# Side_1.net
KiCad netlist of a schematic drawn in EAGLE
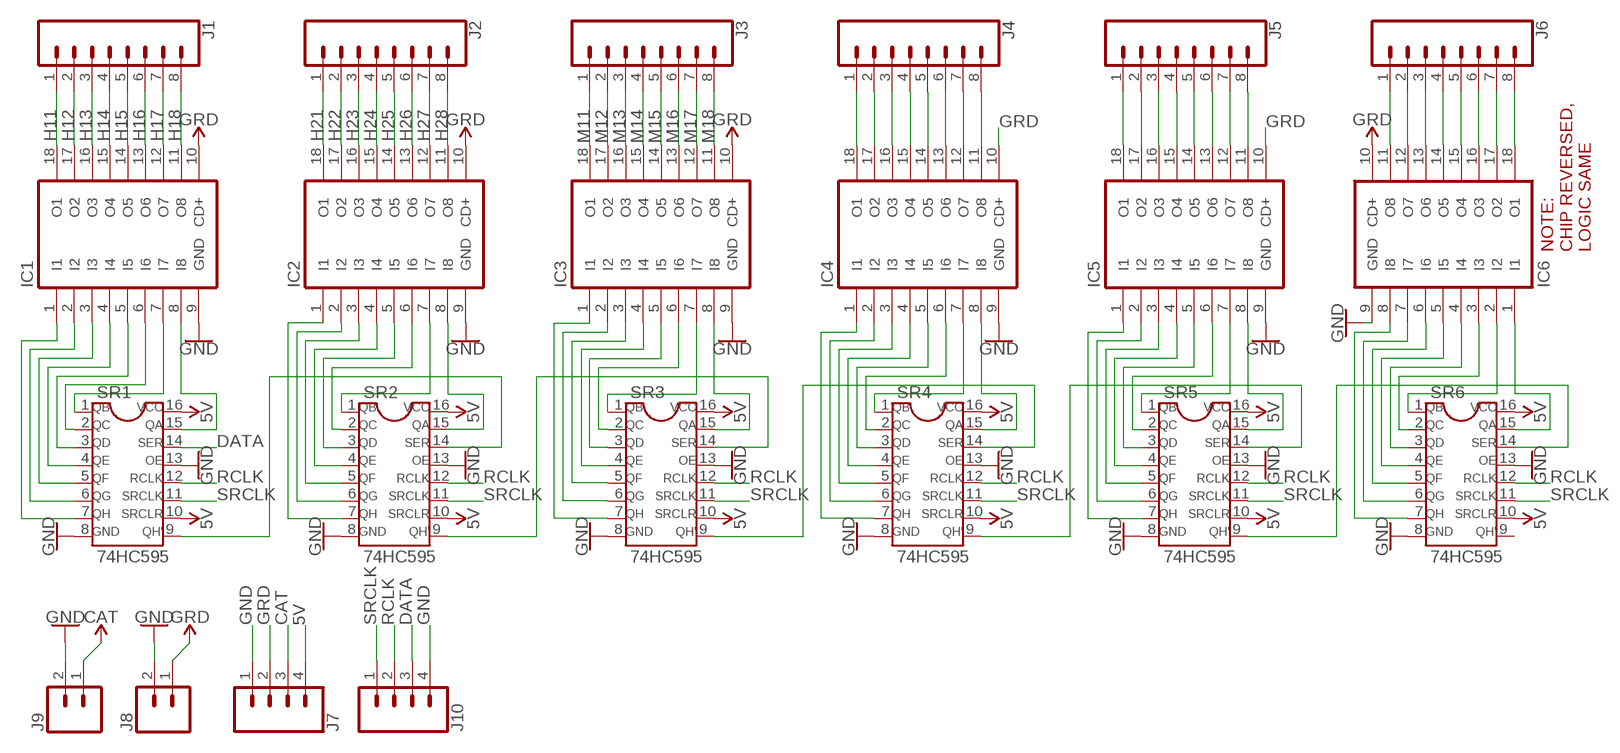
[diagram p0: schematic, sheet 1]

(export (version "E")
  (design (tool "Eeschema 10.0.6"))
  (components
    (comp (ref "IC1")
      (value "ULN2802A")
      (footprint "eagle-import:DIL18")
      (libsource (lib "eagle-import") (part "ULN2802A"))
    )
    (comp (ref "IC2")
      (value "ULN2802A")
      (footprint "eagle-import:DIL18")
      (libsource (lib "eagle-import") (part "ULN2802A"))
    )
    (comp (ref "IC3")
      (value "ULN2802A")
      (footprint "eagle-import:DIL18")
      (libsource (lib "eagle-import") (part "ULN2802A"))
    )
    (comp (ref "IC4")
      (value "ULN2802A")
      (footprint "eagle-import:DIL18")
      (libsource (lib "eagle-import") (part "ULN2802A"))
    )
    (comp (ref "IC5")
      (value "ULN2802A")
      (footprint "eagle-import:DIL18")
      (libsource (lib "eagle-import") (part "ULN2802A"))
    )
    (comp (ref "IC6")
      (value "ULN2802A")
      (footprint "eagle-import:DIL18")
      (libsource (lib "eagle-import") (part "ULN2802A"))
    )
    (comp (ref "J1")
      (value "CONN_08\"")
      (footprint "eagle-import:1X08")
      (libsource (lib "eagle-import") (part "CONN_08{dblquote}"))
    )
    (comp (ref "J2")
      (value "CONN_08\"")
      (footprint "eagle-import:1X08")
      (libsource (lib "eagle-import") (part "CONN_08{dblquote}"))
    )
    (comp (ref "J3")
      (value "CONN_08\"")
      (footprint "eagle-import:1X08")
      (libsource (lib "eagle-import") (part "CONN_08{dblquote}"))
    )
    (comp (ref "J4")
      (value "CONN_08\"")
      (footprint "eagle-import:1X08")
      (libsource (lib "eagle-import") (part "CONN_08{dblquote}"))
    )
    (comp (ref "J5")
      (value "CONN_08\"")
      (footprint "eagle-import:1X08")
      (libsource (lib "eagle-import") (part "CONN_08{dblquote}"))
    )
    (comp (ref "J6")
      (value "CONN_08\"")
      (footprint "eagle-import:1X08")
      (libsource (lib "eagle-import") (part "CONN_08{dblquote}"))
    )
    (comp (ref "J7")
      (value "CONN_04")
      (footprint "eagle-import:1X04")
      (libsource (lib "eagle-import") (part "CONN_04"))
    )
    (comp (ref "J8")
      (value "CONN_02")
      (footprint "eagle-import:1X02")
      (libsource (lib "eagle-import") (part "CONN_02"))
    )
    (comp (ref "J9")
      (value "CONN_02")
      (footprint "eagle-import:1X02")
      (libsource (lib "eagle-import") (part "CONN_02"))
    )
    (comp (ref "J10")
      (value "CONN_04")
      (footprint "eagle-import:1X04")
      (libsource (lib "eagle-import") (part "CONN_04"))
    )
    (comp (ref "SR1")
      (value "74HC595")
      (footprint "eagle-import:DIL16")
      (libsource (lib "eagle-import") (part "74HC595"))
    )
    (comp (ref "SR2")
      (value "74HC595")
      (footprint "eagle-import:DIL16")
      (libsource (lib "eagle-import") (part "74HC595"))
    )
    (comp (ref "SR3")
      (value "74HC595")
      (footprint "eagle-import:DIL16")
      (libsource (lib "eagle-import") (part "74HC595"))
    )
    (comp (ref "SR4")
      (value "74HC595")
      (footprint "eagle-import:DIL16")
      (libsource (lib "eagle-import") (part "74HC595"))
    )
    (comp (ref "SR5")
      (value "74HC595")
      (footprint "eagle-import:DIL16")
      (libsource (lib "eagle-import") (part "74HC595"))
    )
    (comp (ref "SR6")
      (value "74HC595")
      (footprint "eagle-import:DIL16")
      (libsource (lib "eagle-import") (part "74HC595"))
    )
  )
  (nets
    (net (code "1") (name "/DATA") (class "Default")
      (node (ref "J10") (pin "3") (pinfunction "3_3") (pintype "passive"))
      (node (ref "SR1") (pin "14") (pinfunction "SER_14") (pintype "passive"))
    )
    (net (code "2") (name "/H11") (class "Default")
      (node (ref "IC1") (pin "18") (pinfunction "O1_18") (pintype "open_collector"))
      (node (ref "J1") (pin "1") (pinfunction "1_1") (pintype "passive"))
    )
    (net (code "3") (name "/H12") (class "Default")
      (node (ref "IC1") (pin "17") (pinfunction "O2_17") (pintype "open_collector"))
      (node (ref "J1") (pin "2") (pinfunction "2_2") (pintype "passive"))
    )
    (net (code "4") (name "/H13") (class "Default")
      (node (ref "IC1") (pin "16") (pinfunction "O3_16") (pintype "open_collector"))
      (node (ref "J1") (pin "3") (pinfunction "3_3") (pintype "passive"))
    )
    (net (code "5") (name "/H14") (class "Default")
      (node (ref "IC1") (pin "15") (pinfunction "O4_15") (pintype "open_collector"))
      (node (ref "J1") (pin "4") (pinfunction "4_4") (pintype "passive"))
    )
    (net (code "6") (name "/H15") (class "Default")
      (node (ref "IC1") (pin "14") (pinfunction "O5_14") (pintype "open_collector"))
      (node (ref "J1") (pin "5") (pinfunction "5_5") (pintype "passive"))
    )
    (net (code "7") (name "/H16") (class "Default")
      (node (ref "IC1") (pin "13") (pinfunction "O6_13") (pintype "open_collector"))
      (node (ref "J1") (pin "6") (pinfunction "6_6") (pintype "passive"))
    )
    (net (code "8") (name "/H17") (class "Default")
      (node (ref "IC1") (pin "12") (pinfunction "O7_12") (pintype "open_collector"))
      (node (ref "J1") (pin "7") (pinfunction "7_7") (pintype "passive"))
    )
    (net (code "9") (name "/H18") (class "Default")
      (node (ref "IC1") (pin "11") (pinfunction "O8_11") (pintype "open_collector"))
      (node (ref "J1") (pin "8") (pinfunction "8_8") (pintype "passive"))
    )
    (net (code "10") (name "/H21") (class "Default")
      (node (ref "IC2") (pin "18") (pinfunction "O1_18") (pintype "open_collector"))
      (node (ref "J2") (pin "1") (pinfunction "1_1") (pintype "passive"))
    )
    (net (code "11") (name "/H22") (class "Default")
      (node (ref "IC2") (pin "17") (pinfunction "O2_17") (pintype "open_collector"))
      (node (ref "J2") (pin "2") (pinfunction "2_2") (pintype "passive"))
    )
    (net (code "12") (name "/H23") (class "Default")
      (node (ref "IC2") (pin "16") (pinfunction "O3_16") (pintype "open_collector"))
      (node (ref "J2") (pin "3") (pinfunction "3_3") (pintype "passive"))
    )
    (net (code "13") (name "/H24") (class "Default")
      (node (ref "IC2") (pin "15") (pinfunction "O4_15") (pintype "open_collector"))
      (node (ref "J2") (pin "4") (pinfunction "4_4") (pintype "passive"))
    )
    (net (code "14") (name "/H25") (class "Default")
      (node (ref "IC2") (pin "14") (pinfunction "O5_14") (pintype "open_collector"))
      (node (ref "J2") (pin "5") (pinfunction "5_5") (pintype "passive"))
    )
    (net (code "15") (name "/H26") (class "Default")
      (node (ref "IC2") (pin "13") (pinfunction "O6_13") (pintype "open_collector"))
      (node (ref "J2") (pin "6") (pinfunction "6_6") (pintype "passive"))
    )
    (net (code "16") (name "/H27") (class "Default")
      (node (ref "IC2") (pin "12") (pinfunction "O7_12") (pintype "open_collector"))
      (node (ref "J2") (pin "7") (pinfunction "7_7") (pintype "passive"))
    )
    (net (code "17") (name "/H28") (class "Default")
      (node (ref "IC2") (pin "11") (pinfunction "O8_11") (pintype "open_collector"))
      (node (ref "J2") (pin "8") (pinfunction "8_8") (pintype "passive"))
    )
    (net (code "18") (name "/M11") (class "Default")
      (node (ref "IC3") (pin "18") (pinfunction "O1_18") (pintype "open_collector"))
      (node (ref "J3") (pin "1") (pinfunction "1_1") (pintype "passive"))
    )
    (net (code "19") (name "/M12") (class "Default")
      (node (ref "IC3") (pin "17") (pinfunction "O2_17") (pintype "open_collector"))
      (node (ref "J3") (pin "2") (pinfunction "2_2") (pintype "passive"))
    )
    (net (code "20") (name "/M13") (class "Default")
      (node (ref "IC3") (pin "16") (pinfunction "O3_16") (pintype "open_collector"))
      (node (ref "J3") (pin "3") (pinfunction "3_3") (pintype "passive"))
    )
    (net (code "21") (name "/M14") (class "Default")
      (node (ref "IC3") (pin "15") (pinfunction "O4_15") (pintype "open_collector"))
      (node (ref "J3") (pin "4") (pinfunction "4_4") (pintype "passive"))
    )
    (net (code "22") (name "/M15") (class "Default")
      (node (ref "IC3") (pin "14") (pinfunction "O5_14") (pintype "open_collector"))
      (node (ref "J3") (pin "5") (pinfunction "5_5") (pintype "passive"))
    )
    (net (code "23") (name "/M16") (class "Default")
      (node (ref "IC3") (pin "13") (pinfunction "O6_13") (pintype "open_collector"))
      (node (ref "J3") (pin "6") (pinfunction "6_6") (pintype "passive"))
    )
    (net (code "24") (name "/M17") (class "Default")
      (node (ref "IC3") (pin "12") (pinfunction "O7_12") (pintype "open_collector"))
      (node (ref "J3") (pin "7") (pinfunction "7_7") (pintype "passive"))
    )
    (net (code "25") (name "/M18") (class "Default")
      (node (ref "IC3") (pin "11") (pinfunction "O8_11") (pintype "open_collector"))
      (node (ref "J3") (pin "8") (pinfunction "8_8") (pintype "passive"))
    )
    (net (code "26") (name "/RCLK") (class "Default")
      (node (ref "J10") (pin "2") (pinfunction "2_2") (pintype "passive"))
      (node (ref "SR1") (pin "12") (pinfunction "RCLK_12") (pintype "passive"))
      (node (ref "SR2") (pin "12") (pinfunction "RCLK_12") (pintype "passive"))
      (node (ref "SR3") (pin "12") (pinfunction "RCLK_12") (pintype "passive"))
      (node (ref "SR4") (pin "12") (pinfunction "RCLK_12") (pintype "passive"))
      (node (ref "SR5") (pin "12") (pinfunction "RCLK_12") (pintype "passive"))
      (node (ref "SR6") (pin "12") (pinfunction "RCLK_12") (pintype "passive"))
    )
    (net (code "27") (name "/SRCLK") (class "Default")
      (node (ref "J10") (pin "1") (pinfunction "1_1") (pintype "passive"))
      (node (ref "SR1") (pin "11") (pinfunction "SRCLK_11") (pintype "passive"))
      (node (ref "SR2") (pin "11") (pinfunction "SRCLK_11") (pintype "passive"))
      (node (ref "SR3") (pin "11") (pinfunction "SRCLK_11") (pintype "passive"))
      (node (ref "SR4") (pin "11") (pinfunction "SRCLK_11") (pintype "passive"))
      (node (ref "SR5") (pin "11") (pinfunction "SRCLK_11") (pintype "passive"))
      (node (ref "SR6") (pin "11") (pinfunction "SRCLK_11") (pintype "passive"))
    )
    (net (code "28") (name "5V") (class "Default")
      (node (ref "J7") (pin "4") (pinfunction "4_4") (pintype "passive"))
      (node (ref "SR1") (pin "10") (pinfunction "SRCLR_10") (pintype "passive"))
      (node (ref "SR1") (pin "16") (pinfunction "VCC_16") (pintype "passive"))
      (node (ref "SR2") (pin "10") (pinfunction "SRCLR_10") (pintype "passive"))
      (node (ref "SR2") (pin "16") (pinfunction "VCC_16") (pintype "passive"))
      (node (ref "SR3") (pin "10") (pinfunction "SRCLR_10") (pintype "passive"))
      (node (ref "SR3") (pin "16") (pinfunction "VCC_16") (pintype "passive"))
      (node (ref "SR4") (pin "10") (pinfunction "SRCLR_10") (pintype "passive"))
      (node (ref "SR4") (pin "16") (pinfunction "VCC_16") (pintype "passive"))
      (node (ref "SR5") (pin "10") (pinfunction "SRCLR_10") (pintype "passive"))
      (node (ref "SR5") (pin "16") (pinfunction "VCC_16") (pintype "passive"))
      (node (ref "SR6") (pin "10") (pinfunction "SRCLR_10") (pintype "passive"))
      (node (ref "SR6") (pin "16") (pinfunction "VCC_16") (pintype "passive"))
    )
    (net (code "29") (name "CAT") (class "Default")
      (node (ref "J7") (pin "3") (pinfunction "3_3") (pintype "passive"))
      (node (ref "J9") (pin "1") (pinfunction "1_1") (pintype "passive"))
    )
    (net (code "30") (name "GND") (class "Default")
      (node (ref "IC1") (pin "9") (pinfunction "GND_9") (pintype "power_in"))
      (node (ref "IC2") (pin "9") (pinfunction "GND_9") (pintype "power_in"))
      (node (ref "IC3") (pin "9") (pinfunction "GND_9") (pintype "power_in"))
      (node (ref "IC4") (pin "9") (pinfunction "GND_9") (pintype "power_in"))
      (node (ref "IC5") (pin "9") (pinfunction "GND_9") (pintype "power_in"))
      (node (ref "IC6") (pin "9") (pinfunction "GND_9") (pintype "power_in"))
      (node (ref "J10") (pin "4") (pinfunction "4_4") (pintype "passive"))
      (node (ref "J7") (pin "1") (pinfunction "1_1") (pintype "passive"))
      (node (ref "J8") (pin "2") (pinfunction "2_2") (pintype "passive"))
      (node (ref "J9") (pin "2") (pinfunction "2_2") (pintype "passive"))
      (node (ref "SR1") (pin "13") (pinfunction "OE_13") (pintype "passive"))
      (node (ref "SR1") (pin "8") (pinfunction "GND_8") (pintype "passive"))
      (node (ref "SR2") (pin "13") (pinfunction "OE_13") (pintype "passive"))
      (node (ref "SR2") (pin "8") (pinfunction "GND_8") (pintype "passive"))
      (node (ref "SR3") (pin "13") (pinfunction "OE_13") (pintype "passive"))
      (node (ref "SR3") (pin "8") (pinfunction "GND_8") (pintype "passive"))
      (node (ref "SR4") (pin "13") (pinfunction "OE_13") (pintype "passive"))
      (node (ref "SR4") (pin "8") (pinfunction "GND_8") (pintype "passive"))
      (node (ref "SR5") (pin "13") (pinfunction "OE_13") (pintype "passive"))
      (node (ref "SR5") (pin "8") (pinfunction "GND_8") (pintype "passive"))
      (node (ref "SR6") (pin "13") (pinfunction "OE_13") (pintype "passive"))
      (node (ref "SR6") (pin "8") (pinfunction "GND_8") (pintype "passive"))
    )
    (net (code "31") (name "GRD") (class "Default")
      (node (ref "IC1") (pin "10") (pinfunction "CD+_10") (pintype "passive"))
      (node (ref "IC2") (pin "10") (pinfunction "CD+_10") (pintype "passive"))
      (node (ref "IC3") (pin "10") (pinfunction "CD+_10") (pintype "passive"))
      (node (ref "IC4") (pin "10") (pinfunction "CD+_10") (pintype "passive"))
      (node (ref "IC5") (pin "10") (pinfunction "CD+_10") (pintype "passive"))
      (node (ref "IC6") (pin "10") (pinfunction "CD+_10") (pintype "passive"))
      (node (ref "J7") (pin "2") (pinfunction "2_2") (pintype "passive"))
      (node (ref "J8") (pin "1") (pinfunction "1_1") (pintype "passive"))
    )
    (net (code "32") (name "Net-(IC1-I1)") (class "Default")
      (node (ref "IC1") (pin "1") (pinfunction "I1_1") (pintype "input"))
      (node (ref "SR1") (pin "7") (pinfunction "QH_7") (pintype "passive"))
    )
    (net (code "33") (name "Net-(IC1-I2)") (class "Default")
      (node (ref "IC1") (pin "2") (pinfunction "I2_2") (pintype "input"))
      (node (ref "SR1") (pin "6") (pinfunction "QG_6") (pintype "passive"))
    )
    (net (code "34") (name "Net-(IC1-I3)") (class "Default")
      (node (ref "IC1") (pin "3") (pinfunction "I3_3") (pintype "input"))
      (node (ref "SR1") (pin "5") (pinfunction "QF_5") (pintype "passive"))
    )
    (net (code "35") (name "Net-(IC1-I4)") (class "Default")
      (node (ref "IC1") (pin "4") (pinfunction "I4_4") (pintype "input"))
      (node (ref "SR1") (pin "4") (pinfunction "QE_4") (pintype "passive"))
    )
    (net (code "36") (name "Net-(IC1-I5)") (class "Default")
      (node (ref "IC1") (pin "5") (pinfunction "I5_5") (pintype "input"))
      (node (ref "SR1") (pin "3") (pinfunction "QD_3") (pintype "passive"))
    )
    (net (code "37") (name "Net-(IC1-I6)") (class "Default")
      (node (ref "IC1") (pin "6") (pinfunction "I6_6") (pintype "input"))
      (node (ref "SR1") (pin "2") (pinfunction "QC_2") (pintype "passive"))
    )
    (net (code "38") (name "Net-(IC1-I7)") (class "Default")
      (node (ref "IC1") (pin "7") (pinfunction "I7_7") (pintype "input"))
      (node (ref "SR1") (pin "1") (pinfunction "QB_1") (pintype "passive"))
    )
    (net (code "39") (name "Net-(IC1-I8)") (class "Default")
      (node (ref "IC1") (pin "8") (pinfunction "I8_8") (pintype "input"))
      (node (ref "SR1") (pin "15") (pinfunction "QA_15") (pintype "passive"))
    )
    (net (code "40") (name "Net-(IC2-I1)") (class "Default")
      (node (ref "IC2") (pin "1") (pinfunction "I1_1") (pintype "input"))
      (node (ref "SR2") (pin "7") (pinfunction "QH_7") (pintype "passive"))
    )
    (net (code "41") (name "Net-(IC2-I2)") (class "Default")
      (node (ref "IC2") (pin "2") (pinfunction "I2_2") (pintype "input"))
      (node (ref "SR2") (pin "6") (pinfunction "QG_6") (pintype "passive"))
    )
    (net (code "42") (name "Net-(IC2-I3)") (class "Default")
      (node (ref "IC2") (pin "3") (pinfunction "I3_3") (pintype "input"))
      (node (ref "SR2") (pin "5") (pinfunction "QF_5") (pintype "passive"))
    )
    (net (code "43") (name "Net-(IC2-I4)") (class "Default")
      (node (ref "IC2") (pin "4") (pinfunction "I4_4") (pintype "input"))
      (node (ref "SR2") (pin "4") (pinfunction "QE_4") (pintype "passive"))
    )
    (net (code "44") (name "Net-(IC2-I5)") (class "Default")
      (node (ref "IC2") (pin "5") (pinfunction "I5_5") (pintype "input"))
      (node (ref "SR2") (pin "3") (pinfunction "QD_3") (pintype "passive"))
    )
    (net (code "45") (name "Net-(IC2-I6)") (class "Default")
      (node (ref "IC2") (pin "6") (pinfunction "I6_6") (pintype "input"))
      (node (ref "SR2") (pin "2") (pinfunction "QC_2") (pintype "passive"))
    )
    (net (code "46") (name "Net-(IC2-I7)") (class "Default")
      (node (ref "IC2") (pin "7") (pinfunction "I7_7") (pintype "input"))
      (node (ref "SR2") (pin "1") (pinfunction "QB_1") (pintype "passive"))
    )
    (net (code "47") (name "Net-(IC2-I8)") (class "Default")
      (node (ref "IC2") (pin "8") (pinfunction "I8_8") (pintype "input"))
      (node (ref "SR2") (pin "15") (pinfunction "QA_15") (pintype "passive"))
    )
    (net (code "48") (name "Net-(IC3-I1)") (class "Default")
      (node (ref "IC3") (pin "1") (pinfunction "I1_1") (pintype "input"))
      (node (ref "SR3") (pin "7") (pinfunction "QH_7") (pintype "passive"))
    )
    (net (code "49") (name "Net-(IC3-I2)") (class "Default")
      (node (ref "IC3") (pin "2") (pinfunction "I2_2") (pintype "input"))
      (node (ref "SR3") (pin "6") (pinfunction "QG_6") (pintype "passive"))
    )
    (net (code "50") (name "Net-(IC3-I3)") (class "Default")
      (node (ref "IC3") (pin "3") (pinfunction "I3_3") (pintype "input"))
      (node (ref "SR3") (pin "5") (pinfunction "QF_5") (pintype "passive"))
    )
    (net (code "51") (name "Net-(IC3-I4)") (class "Default")
      (node (ref "IC3") (pin "4") (pinfunction "I4_4") (pintype "input"))
      (node (ref "SR3") (pin "4") (pinfunction "QE_4") (pintype "passive"))
    )
    (net (code "52") (name "Net-(IC3-I5)") (class "Default")
      (node (ref "IC3") (pin "5") (pinfunction "I5_5") (pintype "input"))
      (node (ref "SR3") (pin "3") (pinfunction "QD_3") (pintype "passive"))
    )
    (net (code "53") (name "Net-(IC3-I6)") (class "Default")
      (node (ref "IC3") (pin "6") (pinfunction "I6_6") (pintype "input"))
      (node (ref "SR3") (pin "2") (pinfunction "QC_2") (pintype "passive"))
    )
    (net (code "54") (name "Net-(IC3-I7)") (class "Default")
      (node (ref "IC3") (pin "7") (pinfunction "I7_7") (pintype "input"))
      (node (ref "SR3") (pin "1") (pinfunction "QB_1") (pintype "passive"))
    )
    (net (code "55") (name "Net-(IC3-I8)") (class "Default")
      (node (ref "IC3") (pin "8") (pinfunction "I8_8") (pintype "input"))
      (node (ref "SR3") (pin "15") (pinfunction "QA_15") (pintype "passive"))
    )
    (net (code "56") (name "Net-(IC4-I1)") (class "Default")
      (node (ref "IC4") (pin "1") (pinfunction "I1_1") (pintype "input"))
      (node (ref "SR4") (pin "7") (pinfunction "QH_7") (pintype "passive"))
    )
    (net (code "57") (name "Net-(IC4-I2)") (class "Default")
      (node (ref "IC4") (pin "2") (pinfunction "I2_2") (pintype "input"))
      (node (ref "SR4") (pin "6") (pinfunction "QG_6") (pintype "passive"))
    )
    (net (code "58") (name "Net-(IC4-I3)") (class "Default")
      (node (ref "IC4") (pin "3") (pinfunction "I3_3") (pintype "input"))
      (node (ref "SR4") (pin "5") (pinfunction "QF_5") (pintype "passive"))
    )
    (net (code "59") (name "Net-(IC4-I4)") (class "Default")
      (node (ref "IC4") (pin "4") (pinfunction "I4_4") (pintype "input"))
      (node (ref "SR4") (pin "4") (pinfunction "QE_4") (pintype "passive"))
    )
    (net (code "60") (name "Net-(IC4-I5)") (class "Default")
      (node (ref "IC4") (pin "5") (pinfunction "I5_5") (pintype "input"))
      (node (ref "SR4") (pin "3") (pinfunction "QD_3") (pintype "passive"))
    )
    (net (code "61") (name "Net-(IC4-I6)") (class "Default")
      (node (ref "IC4") (pin "6") (pinfunction "I6_6") (pintype "input"))
      (node (ref "SR4") (pin "2") (pinfunction "QC_2") (pintype "passive"))
    )
    (net (code "62") (name "Net-(IC4-I7)") (class "Default")
      (node (ref "IC4") (pin "7") (pinfunction "I7_7") (pintype "input"))
      (node (ref "SR4") (pin "1") (pinfunction "QB_1") (pintype "passive"))
    )
    (net (code "63") (name "Net-(IC4-I8)") (class "Default")
      (node (ref "IC4") (pin "8") (pinfunction "I8_8") (pintype "input"))
      (node (ref "SR4") (pin "15") (pinfunction "QA_15") (pintype "passive"))
    )
    (net (code "64") (name "Net-(IC4-O1)") (class "Default")
      (node (ref "IC4") (pin "18") (pinfunction "O1_18") (pintype "open_collector"))
      (node (ref "J4") (pin "1") (pinfunction "1_1") (pintype "passive"))
    )
    (net (code "65") (name "Net-(IC4-O2)") (class "Default")
      (node (ref "IC4") (pin "17") (pinfunction "O2_17") (pintype "open_collector"))
      (node (ref "J4") (pin "2") (pinfunction "2_2") (pintype "passive"))
    )
    (net (code "66") (name "Net-(IC4-O3)") (class "Default")
      (node (ref "IC4") (pin "16") (pinfunction "O3_16") (pintype "open_collector"))
      (node (ref "J4") (pin "3") (pinfunction "3_3") (pintype "passive"))
    )
    (net (code "67") (name "Net-(IC4-O4)") (class "Default")
      (node (ref "IC4") (pin "15") (pinfunction "O4_15") (pintype "open_collector"))
      (node (ref "J4") (pin "4") (pinfunction "4_4") (pintype "passive"))
    )
    (net (code "68") (name "Net-(IC4-O5)") (class "Default")
      (node (ref "IC4") (pin "14") (pinfunction "O5_14") (pintype "open_collector"))
      (node (ref "J4") (pin "5") (pinfunction "5_5") (pintype "passive"))
    )
    (net (code "69") (name "Net-(IC4-O6)") (class "Default")
      (node (ref "IC4") (pin "13") (pinfunction "O6_13") (pintype "open_collector"))
      (node (ref "J4") (pin "6") (pinfunction "6_6") (pintype "passive"))
    )
    (net (code "70") (name "Net-(IC4-O7)") (class "Default")
      (node (ref "IC4") (pin "12") (pinfunction "O7_12") (pintype "open_collector"))
      (node (ref "J4") (pin "7") (pinfunction "7_7") (pintype "passive"))
    )
    (net (code "71") (name "Net-(IC4-O8)") (class "Default")
      (node (ref "IC4") (pin "11") (pinfunction "O8_11") (pintype "open_collector"))
      (node (ref "J4") (pin "8") (pinfunction "8_8") (pintype "passive"))
    )
    (net (code "72") (name "Net-(IC5-I1)") (class "Default")
      (node (ref "IC5") (pin "1") (pinfunction "I1_1") (pintype "input"))
      (node (ref "SR5") (pin "7") (pinfunction "QH_7") (pintype "passive"))
    )
    (net (code "73") (name "Net-(IC5-I2)") (class "Default")
      (node (ref "IC5") (pin "2") (pinfunction "I2_2") (pintype "input"))
      (node (ref "SR5") (pin "6") (pinfunction "QG_6") (pintype "passive"))
    )
    (net (code "74") (name "Net-(IC5-I3)") (class "Default")
      (node (ref "IC5") (pin "3") (pinfunction "I3_3") (pintype "input"))
      (node (ref "SR5") (pin "5") (pinfunction "QF_5") (pintype "passive"))
    )
    (net (code "75") (name "Net-(IC5-I4)") (class "Default")
      (node (ref "IC5") (pin "4") (pinfunction "I4_4") (pintype "input"))
      (node (ref "SR5") (pin "4") (pinfunction "QE_4") (pintype "passive"))
    )
    (net (code "76") (name "Net-(IC5-I5)") (class "Default")
      (node (ref "IC5") (pin "5") (pinfunction "I5_5") (pintype "input"))
      (node (ref "SR5") (pin "3") (pinfunction "QD_3") (pintype "passive"))
    )
    (net (code "77") (name "Net-(IC5-I6)") (class "Default")
      (node (ref "IC5") (pin "6") (pinfunction "I6_6") (pintype "input"))
      (node (ref "SR5") (pin "2") (pinfunction "QC_2") (pintype "passive"))
    )
    (net (code "78") (name "Net-(IC5-I7)") (class "Default")
      (node (ref "IC5") (pin "7") (pinfunction "I7_7") (pintype "input"))
      (node (ref "SR5") (pin "1") (pinfunction "QB_1") (pintype "passive"))
    )
    (net (code "79") (name "Net-(IC5-I8)") (class "Default")
      (node (ref "IC5") (pin "8") (pinfunction "I8_8") (pintype "input"))
      (node (ref "SR5") (pin "15") (pinfunction "QA_15") (pintype "passive"))
    )
    (net (code "80") (name "Net-(IC5-O1)") (class "Default")
      (node (ref "IC5") (pin "18") (pinfunction "O1_18") (pintype "open_collector"))
      (node (ref "J5") (pin "1") (pinfunction "1_1") (pintype "passive"))
    )
    (net (code "81") (name "Net-(IC5-O2)") (class "Default")
      (node (ref "IC5") (pin "17") (pinfunction "O2_17") (pintype "open_collector"))
      (node (ref "J5") (pin "2") (pinfunction "2_2") (pintype "passive"))
    )
    (net (code "82") (name "Net-(IC5-O3)") (class "Default")
      (node (ref "IC5") (pin "16") (pinfunction "O3_16") (pintype "open_collector"))
      (node (ref "J5") (pin "3") (pinfunction "3_3") (pintype "passive"))
    )
    (net (code "83") (name "Net-(IC5-O4)") (class "Default")
      (node (ref "IC5") (pin "15") (pinfunction "O4_15") (pintype "open_collector"))
      (node (ref "J5") (pin "4") (pinfunction "4_4") (pintype "passive"))
    )
    (net (code "84") (name "Net-(IC5-O5)") (class "Default")
      (node (ref "IC5") (pin "14") (pinfunction "O5_14") (pintype "open_collector"))
      (node (ref "J5") (pin "5") (pinfunction "5_5") (pintype "passive"))
    )
    (net (code "85") (name "Net-(IC5-O6)") (class "Default")
      (node (ref "IC5") (pin "13") (pinfunction "O6_13") (pintype "open_collector"))
      (node (ref "J5") (pin "6") (pinfunction "6_6") (pintype "passive"))
    )
    (net (code "86") (name "Net-(IC5-O7)") (class "Default")
      (node (ref "IC5") (pin "12") (pinfunction "O7_12") (pintype "open_collector"))
      (node (ref "J5") (pin "7") (pinfunction "7_7") (pintype "passive"))
    )
    (net (code "87") (name "Net-(IC5-O8)") (class "Default")
      (node (ref "IC5") (pin "11") (pinfunction "O8_11") (pintype "open_collector"))
      (node (ref "J5") (pin "8") (pinfunction "8_8") (pintype "passive"))
    )
    (net (code "88") (name "Net-(IC6-I1)") (class "Default")
      (node (ref "IC6") (pin "1") (pinfunction "I1_1") (pintype "input"))
      (node (ref "SR6") (pin "15") (pinfunction "QA_15") (pintype "passive"))
    )
    (net (code "89") (name "Net-(IC6-I2)") (class "Default")
      (node (ref "IC6") (pin "2") (pinfunction "I2_2") (pintype "input"))
      (node (ref "SR6") (pin "1") (pinfunction "QB_1") (pintype "passive"))
    )
    (net (code "90") (name "Net-(IC6-I3)") (class "Default")
      (node (ref "IC6") (pin "3") (pinfunction "I3_3") (pintype "input"))
      (node (ref "SR6") (pin "2") (pinfunction "QC_2") (pintype "passive"))
    )
    (net (code "91") (name "Net-(IC6-I4)") (class "Default")
      (node (ref "IC6") (pin "4") (pinfunction "I4_4") (pintype "input"))
      (node (ref "SR6") (pin "3") (pinfunction "QD_3") (pintype "passive"))
    )
    (net (code "92") (name "Net-(IC6-I5)") (class "Default")
      (node (ref "IC6") (pin "5") (pinfunction "I5_5") (pintype "input"))
      (node (ref "SR6") (pin "4") (pinfunction "QE_4") (pintype "passive"))
    )
    (net (code "93") (name "Net-(IC6-I6)") (class "Default")
      (node (ref "IC6") (pin "6") (pinfunction "I6_6") (pintype "input"))
      (node (ref "SR6") (pin "5") (pinfunction "QF_5") (pintype "passive"))
    )
    (net (code "94") (name "Net-(IC6-I7)") (class "Default")
      (node (ref "IC6") (pin "7") (pinfunction "I7_7") (pintype "input"))
      (node (ref "SR6") (pin "6") (pinfunction "QG_6") (pintype "passive"))
    )
    (net (code "95") (name "Net-(IC6-I8)") (class "Default")
      (node (ref "IC6") (pin "8") (pinfunction "I8_8") (pintype "input"))
      (node (ref "SR6") (pin "7") (pinfunction "QH_7") (pintype "passive"))
    )
    (net (code "96") (name "Net-(IC6-O1)") (class "Default")
      (node (ref "IC6") (pin "18") (pinfunction "O1_18") (pintype "open_collector"))
      (node (ref "J6") (pin "8") (pinfunction "8_8") (pintype "passive"))
    )
    (net (code "97") (name "Net-(IC6-O2)") (class "Default")
      (node (ref "IC6") (pin "17") (pinfunction "O2_17") (pintype "open_collector"))
      (node (ref "J6") (pin "7") (pinfunction "7_7") (pintype "passive"))
    )
    (net (code "98") (name "Net-(IC6-O3)") (class "Default")
      (node (ref "IC6") (pin "16") (pinfunction "O3_16") (pintype "open_collector"))
      (node (ref "J6") (pin "6") (pinfunction "6_6") (pintype "passive"))
    )
    (net (code "99") (name "Net-(IC6-O4)") (class "Default")
      (node (ref "IC6") (pin "15") (pinfunction "O4_15") (pintype "open_collector"))
      (node (ref "J6") (pin "5") (pinfunction "5_5") (pintype "passive"))
    )
    (net (code "100") (name "Net-(IC6-O5)") (class "Default")
      (node (ref "IC6") (pin "14") (pinfunction "O5_14") (pintype "open_collector"))
      (node (ref "J6") (pin "4") (pinfunction "4_4") (pintype "passive"))
    )
    (net (code "101") (name "Net-(IC6-O6)") (class "Default")
      (node (ref "IC6") (pin "13") (pinfunction "O6_13") (pintype "open_collector"))
      (node (ref "J6") (pin "3") (pinfunction "3_3") (pintype "passive"))
    )
    (net (code "102") (name "Net-(IC6-O7)") (class "Default")
      (node (ref "IC6") (pin "12") (pinfunction "O7_12") (pintype "open_collector"))
      (node (ref "J6") (pin "2") (pinfunction "2_2") (pintype "passive"))
    )
    (net (code "103") (name "Net-(IC6-O8)") (class "Default")
      (node (ref "IC6") (pin "11") (pinfunction "O8_11") (pintype "open_collector"))
      (node (ref "J6") (pin "1") (pinfunction "1_1") (pintype "passive"))
    )
    (net (code "104") (name "Net-(SR1-QH')") (class "Default")
      (node (ref "SR1") (pin "9") (pinfunction "QH'_9") (pintype "passive"))
      (node (ref "SR2") (pin "14") (pinfunction "SER_14") (pintype "passive"))
    )
    (net (code "105") (name "Net-(SR2-QH')") (class "Default")
      (node (ref "SR2") (pin "9") (pinfunction "QH'_9") (pintype "passive"))
      (node (ref "SR3") (pin "14") (pinfunction "SER_14") (pintype "passive"))
    )
    (net (code "106") (name "Net-(SR3-QH')") (class "Default")
      (node (ref "SR3") (pin "9") (pinfunction "QH'_9") (pintype "passive"))
      (node (ref "SR4") (pin "14") (pinfunction "SER_14") (pintype "passive"))
    )
    (net (code "107") (name "Net-(SR4-QH')") (class "Default")
      (node (ref "SR4") (pin "9") (pinfunction "QH'_9") (pintype "passive"))
      (node (ref "SR5") (pin "14") (pinfunction "SER_14") (pintype "passive"))
    )
    (net (code "108") (name "Net-(SR5-QH')") (class "Default")
      (node (ref "SR5") (pin "9") (pinfunction "QH'_9") (pintype "passive"))
      (node (ref "SR6") (pin "14") (pinfunction "SER_14") (pintype "passive"))
    )
    (net (code "109") (name "unconnected-(SR6-QH'-Pad9)") (class "Default")
      (node (ref "SR6") (pin "9") (pinfunction "QH'_9") (pintype "passive"))
    )
  )
)
